# Home_Automation.net
KiCad netlist of a schematic drawn in Altium Designer
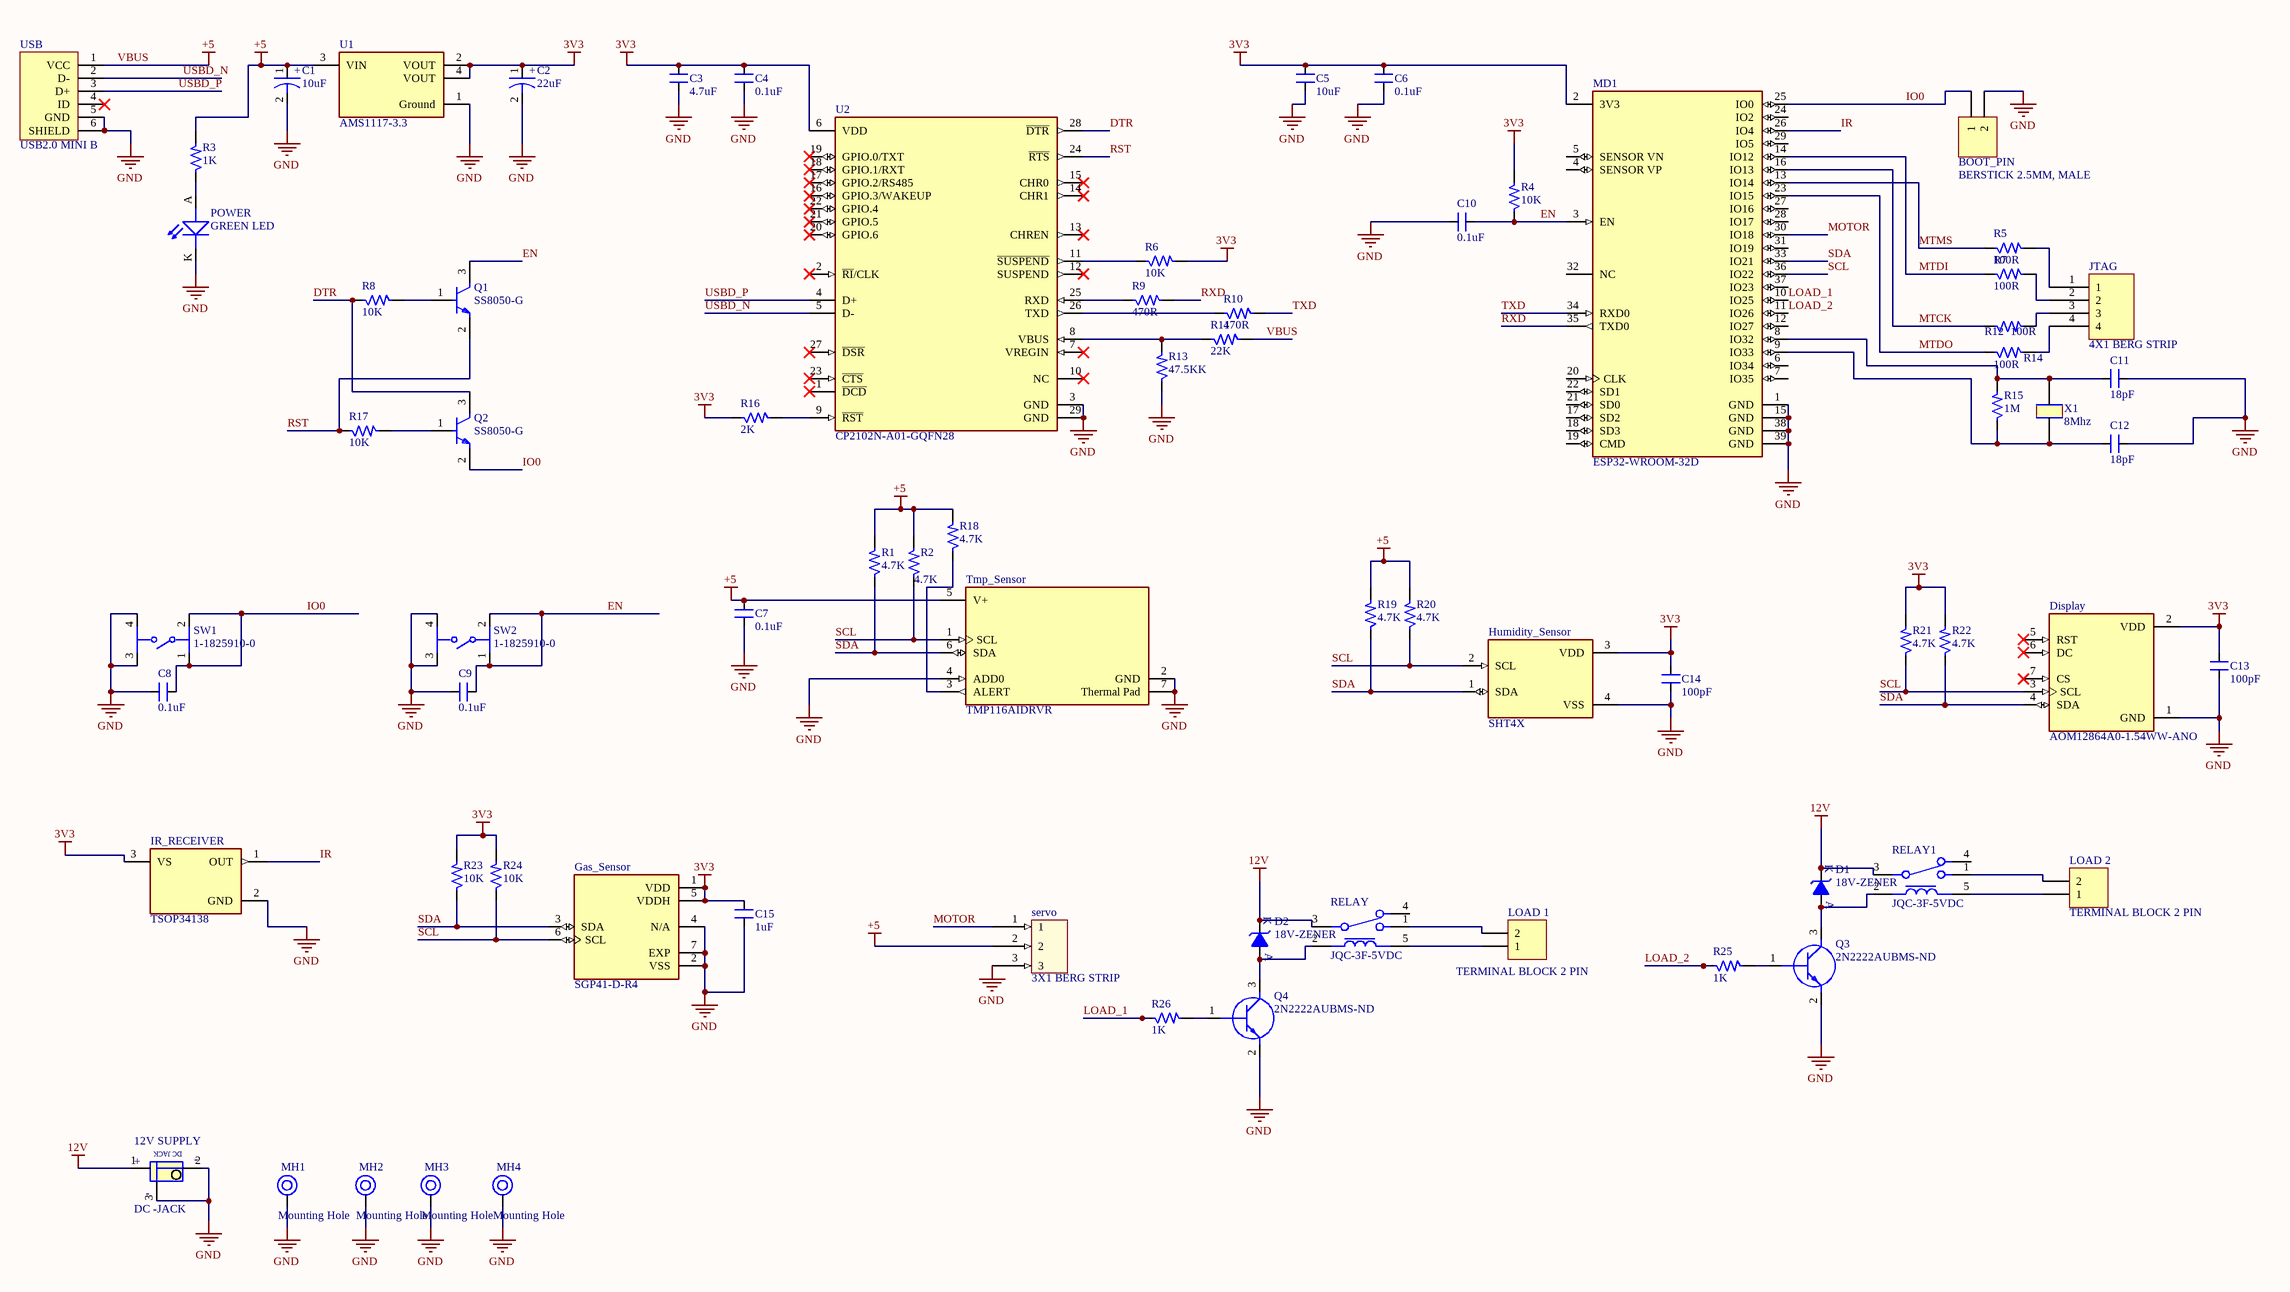
[diagram p0: Home_Automation.SchDoc]

(export (version "E")
  (design (tool "Eeschema 10.0.6"))
  (components
    (comp (ref "12V SUPPLY")
      (value "DC -JACK")
      (footprint "CON3_129_PJ-002A_TH_RA")
      (description "3 Pins, 1 Row 228mil Pitch, right angle Connector, male")
      (fields (field (name "MANUFACTURER") "JST") (field (name "MANUFACTURER PART NUMBER") "PJ-002A"))
      (libsource (lib "ESTEEMPCBLIB") (part "CON-PLG_3X1-228-DC_JACK"))
    )
    (comp (ref "BOOT_PIN")
      (value "BERSTICK 2.5MM, MALE")
      (footprint "CON2_100_43D62_TH_ST")
      (description "2 Pins, 1 Row 2.54mm Pitch, Straight bergstrip, Male")
      (fields (field (name "MANUFACTURER PART NUMBER") "NA") (field (name "MANUFACTURER") "Samtec"))
      (libsource (lib "ESTEEMPCBLIB") (part "CON-BS-PLG_2X1-100-ST-TH"))
    )
    (comp (ref "C1")
      (value "10uF")
      (footprint "ACAP_P339_D393_H531_RAD")
      (description "10µF 400V Aluminum Electrolytic Capacitors Radial, Can - SMD 10000 Hrs @ 105°C")
      (fields
        (field (name "MANUFACTURER") "Nichicon")
        (field (name "MANUFACTURER PART NUMBER") "ULV2G100MNL1GS")
      )
      (libsource (lib "ESTEEMPCBLIB") (part "CAP-P_10uF-400V-20%-RAD"))
    )
    (comp (ref "C2")
      (value "22uF")
      (footprint "ACAP_P339_D393_H531_RAD")
      (description "22µF 400V Aluminum Electrolytic Capacitors Radial, Can - SMD 5000 Hrs @ 105°C")
      (fields
        (field (name "MANUFACTURER") "Panasonic Electronic Components")
        (field (name "MANUFACTURER PART NUMBER") "EEV-EB2G220M")
      )
      (libsource (lib "ESTEEMPCBLIB") (part "CAP-P_22uF-400V-20%-RAD"))
    )
    (comp (ref "C3")
      (value "4.7uF")
      (footprint "CAP_0805")
      (description "4.7µF ±10% 50V Ceramic Capacitor X5R 0805 (2012 Metric)")
      (fields
        (field (name "MANUFACTURER") "Yageo")
        (field (name "MANUFACTURER PART NUMBER") "GRM21BR61H475KE51L")
      )
      (libsource (lib "ESTEEMPCBLIB") (part "CAP_4.7uF-50V-10%-0805"))
    )
    (comp (ref "C4")
      (value "0.1uF")
      (footprint "CAP_0805")
      (description "0.1µF ±10% 50V Ceramic Capacitor X7R 0805 (2012 Metric)")
      (fields
        (field (name "MANUFACTURER") "Samsung")
        (field (name "MANUFACTURER PART NUMBER") "CL21B104KBCNNNC")
      )
      (libsource (lib "ESTEEMPCBLIB") (part "CAP_0.1uF-50V-10%-0805"))
    )
    (comp (ref "C5")
      (value "10uF")
      (footprint "CAP_0805")
      (description "100pF ±5% 100V Ceramic Capacitor C0G, NP0 0805 (2012 Metric)")
      (fields
        (field (name "MANUFACTURER") "Murata")
        (field (name "MANUFACTURER PART NUMBER") "CL21C101JC61PNC")
      )
      (libsource (lib "ESTEEMPCBLIB") (part "CAP_100pF-100V-5%-0805"))
    )
    (comp (ref "C6")
      (value "0.1uF")
      (footprint "CAP_0805")
      (description "0.1µF ±5% 50V Ceramic Capacitor X7R 0805 (2012 Metric)")
      (fields
        (field (name "MANUFACTURER") "AVX Corporation")
        (field (name "MANUFACTURER PART NUMBER") "08055C104JAT4A")
      )
      (libsource (lib "ESTEEMPCBLIB") (part "CAP_0.1uF-50V-5%-0805"))
    )
    (comp (ref "C7")
      (value "0.1uF")
      (footprint "CAP_0805")
      (description "0.1µF ±5% 50V Ceramic Capacitor X7R 0805 (2012 Metric)")
      (fields
        (field (name "MANUFACTURER") "AVX Corporation")
        (field (name "MANUFACTURER PART NUMBER") "08055C104JAT4A")
      )
      (libsource (lib "ESTEEMPCBLIB") (part "CAP_0.1uF-50V-5%-0805"))
    )
    (comp (ref "C8")
      (value "0.1uF")
      (footprint "CAP_0805")
      (description "0.1µF ±5% 50V Ceramic Capacitor X7R 0805 (2012 Metric)")
      (fields
        (field (name "MANUFACTURER") "AVX Corporation")
        (field (name "MANUFACTURER PART NUMBER") "08055C104JAT4A")
      )
      (libsource (lib "ESTEEMPCBLIB") (part "CAP_0.1uF-50V-5%-0805"))
    )
    (comp (ref "C9")
      (value "0.1uF")
      (footprint "CAP_0805")
      (description "0.1µF ±5% 50V Ceramic Capacitor X7R 0805 (2012 Metric)")
      (fields
        (field (name "MANUFACTURER") "AVX Corporation")
        (field (name "MANUFACTURER PART NUMBER") "08055C104JAT4A")
      )
      (libsource (lib "ESTEEMPCBLIB") (part "CAP_0.1uF-50V-5%-0805"))
    )
    (comp (ref "C10")
      (value "0.1uF")
      (footprint "CAP_0805")
      (description "0.1µF ±5% 50V Ceramic Capacitor X7R 0805 (2012 Metric)")
      (fields
        (field (name "MANUFACTURER") "AVX Corporation")
        (field (name "MANUFACTURER PART NUMBER") "08055C104JAT4A")
      )
      (libsource (lib "ESTEEMPCBLIB") (part "CAP_0.1uF-50V-5%-0805"))
    )
    (comp (ref "C11")
      (value "18pF")
      (footprint "CAP_0805")
      (description "18pF ±5% 50V Ceramic Capacitor C0G, NP0 0805 (2012 Metric)")
      (fields
        (field (name "MANUFACTURER") "Yageo")
        (field (name "MANUFACTURER PART NUMBER") "CL21C180JBANNNC")
      )
      (libsource (lib "ESTEEMPCBLIB") (part "CAP_18pF-50V-5%-0805"))
    )
    (comp (ref "C12")
      (value "18pF")
      (footprint "CAP_0805")
      (description "18pF ±5% 50V Ceramic Capacitor C0G, NP0 0805 (2012 Metric)")
      (fields
        (field (name "MANUFACTURER") "Yageo")
        (field (name "MANUFACTURER PART NUMBER") "CL21C180JBANNNC")
      )
      (libsource (lib "ESTEEMPCBLIB") (part "CAP_18pF-50V-5%-0805"))
    )
    (comp (ref "C13")
      (value "100pF")
      (footprint "CAP_0805")
      (description "100pF ±5% 100V Ceramic Capacitor C0G, NP0 0805 (2012 Metric)")
      (fields
        (field (name "MANUFACTURER") "Murata")
        (field (name "MANUFACTURER PART NUMBER") "CL21C101JC61PNC")
      )
      (libsource (lib "ESTEEMPCBLIB") (part "CAP_100pF-100V-5%-0805"))
    )
    (comp (ref "C14")
      (value "100pF")
      (footprint "CAP_0805")
      (description "100pF ±5% 100V Ceramic Capacitor C0G, NP0 0805 (2012 Metric)")
      (fields
        (field (name "MANUFACTURER") "Murata")
        (field (name "MANUFACTURER PART NUMBER") "CL21C101JC61PNC")
      )
      (libsource (lib "ESTEEMPCBLIB") (part "CAP_100pF-100V-5%-0805"))
    )
    (comp (ref "C15")
      (value "1uF")
      (footprint "CAP_0805")
      (description "1µF ±5% 50V Ceramic Capacitor X7R 0805 (2012 Metric)")
      (fields
        (field (name "MANUFACTURER") "Samsung")
        (field (name "MANUFACTURER PART NUMBER") "CC0805JKX7R9BB105")
      )
      (libsource (lib "ESTEEMPCBLIB") (part "CAP_1uF-50V-5%-0805"))
    )
    (comp (ref "D1")
      (value "18V-ZENER")
      (footprint "DIO_SOD80C")
      (description "Zener Diode 18V 500mW ±5% Surface Mount SOD-80 QuadroMELF")
      (fields
        (field (name "MANUFACTURER") "Vishay Semiconductors")
        (field (name "MANUFACTURER PART NUMBER") "BZT55C18-GS08")
      )
      (libsource (lib "ESTEEMPCBLIB") (part "DIO-Z_18V-500mW-SOD80"))
    )
    (comp (ref "D2")
      (value "18V-ZENER")
      (footprint "DIO_SOD80C")
      (description "Zener Diode 18V 500mW ±5% Surface Mount SOD-80 QuadroMELF")
      (fields
        (field (name "MANUFACTURER") "Vishay Semiconductors")
        (field (name "MANUFACTURER PART NUMBER") "BZT55C18-GS08")
      )
      (libsource (lib "ESTEEMPCBLIB") (part "DIO-Z_18V-500mW-SOD80"))
    )
    (comp (ref "Display")
      (value "AOM12864A0-1.54WW-ANO")
      (footprint "LCD_AOM12864A0-1.54WW-ANO")
      (description "Non-Touch Graphic LCD Display Module - White OLED SPI 1.54 (39.12mm) 128 x 64")
      (fields (field (name "MF") "Orient Display"))
      (libsource (lib "AOM12864A0-1.54WW-ANO") (part "AOM12864A0-1.54WW-ANO"))
    )
    (comp (ref "Gas_Sensor")
      (value "SGP41-D-R4")
      (footprint "XDCR_SGP41-D-R4")
      (description "Air Quality Sensor VOC and NOx Gas Sensor 3.3V 6-Pin DFN EP")
      (fields (field (name "MF") "Sensirion"))
      (libsource (lib "SGP41-D-R4") (part "SGP41-D-R4"))
    )
    (comp (ref "Humidity_Sensor")
      (value "SHT4X")
      (footprint "SHT4X")
      (description "Digital Relative Humidity Temperature Sensor, Â±1.0 %RH, Â±0.1 Â°C, Ultra-Low-Power")
      (fields (field (name "MF") "Sensirion") (field (name "MP") "SHT45-AD1B-R2"))
      (libsource (lib "SHT4X") (part "SHT4X"))
    )
    (comp (ref "IR_RECEIVER")
      (value "TSOP34138")
      (footprint "FP-6_550-5169_01-4-MFG")
      (description "SENSOR REMOTE REC 38.0KHZ 45M")
      (fields
        (field (name "MANUFACTURER") "Vishay")
        (field (name "OCTOPART") "https://octopart.com/tsop34138-vishay-55433998")
      )
      (libsource (lib "Altium Content Vault") (part "67e88e076711625980e7b323ec594be"))
    )
    (comp (ref "JTAG")
      (value "4X1 BERG STRIP")
      (footprint "CON4_100_40D72_TH_ST_MALE")
      (description "4 Pins, 1 Row 2.54mm Pitch, Straight bergstrip, Male")
      (fields (field (name "MANUFACTURER") "NA"))
      (libsource (lib "ESTEEMPCBLIB") (part "CON-BS-PLG_4X1-100-ST-TH"))
    )
    (comp (ref "LOAD 1")
      (value "TERMINAL BLOCK 2 PIN")
      (footprint "CON2_P196_1729128_TH_ST")
      (description "2 Pins, 1 Row 5mm Pitch, straight Connector, male")
      (fields
        (field (name "MANUFACTURER") "Phoenix Contact")
        (field (name "MANUFACTURER PART NUMBER") "MKDSN1,5/2")
      )
      (libsource (lib "ESTEEMPCBLIB") (part "CON-TB_2X1-196-ST-TH"))
    )
    (comp (ref "LOAD 2")
      (value "TERMINAL BLOCK 2 PIN")
      (footprint "CON2_P196_1729128_TH_ST")
      (description "2 Pins, 1 Row 5mm Pitch, straight Connector, male")
      (fields
        (field (name "MANUFACTURER") "Phoenix Contact")
        (field (name "MANUFACTURER PART NUMBER") "MKDSN1,5/2")
      )
      (libsource (lib "ESTEEMPCBLIB") (part "CON-TB_2X1-196-ST-TH"))
    )
    (comp (ref "MD1")
      (value "ESP32-WROOM-32D")
      (footprint "FP-ESP32-WROOM-32D-MFG")
      (description "WIFI MODULE 32MBITS SPI FLASH")
      (fields
        (field (name "OCTOPART") "https://octopart.com/esp32-wroom-32d-espressif+systems-91040050")
        (field (name "MANUFACTURER") "Espressif Systems")
      )
      (libsource (lib "Altium Content Vault") (part "a031a76f8c27026a7a7f4657ff233a3"))
    )
    (comp (ref "MH1")
      (value "Mounting Hole")
      (footprint "MOUNTING")
      (fields (field (name "MANUFACTURER PART NUMBER") "NA"))
      (libsource (lib "ESTEEMPCBLIB") (part "MH_3.5H_6D"))
    )
    (comp (ref "MH2")
      (value "Mounting Hole")
      (footprint "MOUNTING")
      (fields (field (name "MANUFACTURER PART NUMBER") "NA"))
      (libsource (lib "ESTEEMPCBLIB") (part "MH_3.5H_6D"))
    )
    (comp (ref "MH3")
      (value "Mounting Hole")
      (footprint "MOUNTING")
      (fields (field (name "MANUFACTURER PART NUMBER") "NA"))
      (libsource (lib "ESTEEMPCBLIB") (part "MH_3.5H_6D"))
    )
    (comp (ref "MH4")
      (value "Mounting Hole")
      (footprint "MOUNTING")
      (fields (field (name "MANUFACTURER PART NUMBER") "NA"))
      (libsource (lib "ESTEEMPCBLIB") (part "MH_3.5H_6D"))
    )
    (comp (ref "POWER")
      (value "GREEN LED")
      (footprint "LED_0805")
      (description "Green 569nm LED Indication - Discrete 2.1V 0805 (2012 Metric)")
      (fields
        (field (name "MANUFACTURER") "Vishay Lite-On")
        (field (name "MANUFACTURER PART NUMBER") "LTST-C171GKT")
      )
      (libsource (lib "ESTEEMPCBLIB") (part "LED_GREEN-2.2-20mA-0805"))
    )
    (comp (ref "Q1")
      (value "SS8050-G")
      (footprint "FP-SS8050-G-MFG")
      (description "NPN TRANSISTOR 1.5A 40V SOT-23 R")
      (libsource (lib "Altium Content Vault") (part "2a1388f82443b098dcd57d24ac7632d"))
    )
    (comp (ref "Q2")
      (value "SS8050-G")
      (footprint "FP-SS8050-G-MFG")
      (description "NPN TRANSISTOR 1.5A 40V SOT-23 R")
      (libsource (lib "Altium Content Vault") (part "2a1388f82443b098dcd57d24ac7632d"))
    )
    (comp (ref "Q3")
      (value "2N2222AUBMS-ND")
      (footprint "SOT 23-3")
      (description "Bipolar (BJT) Transistor NPN 50V 800mA 500mW Surface Mount 3-SMD")
      (fields (field (name "MANUFACTURER") "Microsemi") (field (name "MANUFACTURER PART NUMBER") "2N2222AUB"))
      (libsource (lib "ESTEEMPCBLIB") (part "TRNS-NPN_50V-0.8A-3SMD"))
    )
    (comp (ref "Q4")
      (value "2N2222AUBMS-ND")
      (footprint "SOT 23-3")
      (description "Bipolar (BJT) Transistor NPN 50V 800mA 500mW Surface Mount 3-SMD")
      (fields (field (name "MANUFACTURER") "Microsemi") (field (name "MANUFACTURER PART NUMBER") "2N2222AUB"))
      (libsource (lib "ESTEEMPCBLIB") (part "TRNS-NPN_50V-0.8A-3SMD"))
    )
    (comp (ref "R1")
      (value "4.7K")
      (footprint "RES_0805")
      (description "4.7 kOhms ±1% 0.125W, 1/8W Chip Resistor 0805 (2012 Metric) Moisture Resistant Thick Film")
      (fields
        (field (name "MANUFACTURER") "TE Connectivity")
        (field (name "MANUFACTURER PART NUMBER") "RC0805FR-074K7L")
      )
      (libsource (lib "ESTEEMPCBLIB") (part "RES_4.7K-0.125W-1%-0805"))
    )
    (comp (ref "R2")
      (value "4.7K")
      (footprint "RES_0805")
      (description "4.7 kOhms ±1% 0.125W, 1/8W Chip Resistor 0805 (2012 Metric) Moisture Resistant Thick Film")
      (fields
        (field (name "MANUFACTURER") "TE Connectivity")
        (field (name "MANUFACTURER PART NUMBER") "RC0805FR-074K7L")
      )
      (libsource (lib "ESTEEMPCBLIB") (part "RES_4.7K-0.125W-1%-0805"))
    )
    (comp (ref "R3")
      (value "1K")
      (footprint "RES_0805")
      (description "1 kOhms ±1% 0.125W, 1/8W Chip Resistor 0805 (2012 Metric) Moisture Resistant Thick Film")
      (fields (field (name "MANUFACTURER") "Walsin") (field (name "MANUFACTURER PART NUMBER") "WR08X1001FTL"))
      (libsource (lib "ESTEEMPCBLIB") (part "RES_1K-0.125W-1%-0805"))
    )
    (comp (ref "R4")
      (value "10K")
      (footprint "RES_0805")
      (description "10 kOhms ±1% 0.125W, 1/8W Chip Resistor 0805 (2012 Metric) Automotive AEC-Q200 Thick Film")
      (fields (field (name "MANUFACTURER") "CTS") (field (name "MANUFACTURER PART NUMBER") "WR08X1002FTL"))
      (libsource (lib "ESTEEMPCBLIB") (part "RES_10K-0.125W-1%-0805"))
    )
    (comp (ref "R5")
      (value "100R")
      (footprint "RES_0805")
      (fields (field (name "MANUFACTURER") "Walsin") (field (name "MANUFACTURER PART NUMBER") "WR08X1000FTL"))
      (libsource (lib "ESTEEMPCBLIB") (part "RES_100R-0.125W-1%-0805"))
    )
    (comp (ref "R6")
      (value "10K")
      (footprint "RES_0805")
      (description "10 kOhms ±1% 0.125W, 1/8W Chip Resistor 0805 (2012 Metric) Automotive AEC-Q200 Thick Film")
      (fields (field (name "MANUFACTURER") "CTS") (field (name "MANUFACTURER PART NUMBER") "WR08X1002FTL"))
      (libsource (lib "ESTEEMPCBLIB") (part "RES_10K-0.125W-1%-0805"))
    )
    (comp (ref "R7")
      (value "100R")
      (footprint "RES_0805")
      (fields (field (name "MANUFACTURER") "Walsin") (field (name "MANUFACTURER PART NUMBER") "WR08X1000FTL"))
      (libsource (lib "ESTEEMPCBLIB") (part "RES_100R-0.125W-1%-0805"))
    )
    (comp (ref "R8")
      (value "10K")
      (footprint "RES_0805")
      (description "10 kOhms ±1% 0.125W, 1/8W Chip Resistor 0805 (2012 Metric) Automotive AEC-Q200 Thick Film")
      (fields (field (name "MANUFACTURER") "CTS") (field (name "MANUFACTURER PART NUMBER") "WR08X1002FTL"))
      (libsource (lib "ESTEEMPCBLIB") (part "RES_10K-0.125W-1%-0805"))
    )
    (comp (ref "R9")
      (value "470R")
      (footprint "RES_0805")
      (description "470 Ohms ±1% 0.125W, 1/8W Chip Resistor 0805 (2012 Metric) Automotive AEC-Q200 Thick Film")
      (fields (field (name "MANUFACTURER") "Walsin") (field (name "MANUFACTURER PART NUMBER") "WR08X4700FTL"))
      (libsource (lib "ESTEEMPCBLIB") (part "RES_470R-0.125W-1%-0805"))
    )
    (comp (ref "R10")
      (value "470R")
      (footprint "RES_0805")
      (description "470 Ohms ±1% 0.125W, 1/8W Chip Resistor 0805 (2012 Metric) Automotive AEC-Q200 Thick Film")
      (fields (field (name "MANUFACTURER") "Walsin") (field (name "MANUFACTURER PART NUMBER") "WR08X4700FTL"))
      (libsource (lib "ESTEEMPCBLIB") (part "RES_470R-0.125W-1%-0805"))
    )
    (comp (ref "R11")
      (value "22K")
      (footprint "RES_0805")
      (description "22 kOhms ±1% 0.125W, 1/8W Chip Resistor 0805 (2012 Metric) Automotive AEC-Q200 Thick Film")
      (fields (field (name "MANUFACTURER") "Walsin") (field (name "MANUFACTURER PART NUMBER") "WR08X2202FTL"))
      (libsource (lib "ESTEEMPCBLIB") (part "RES_22K-0.125W-1%-0805"))
    )
    (comp (ref "R12")
      (value "100R")
      (footprint "RES_0805")
      (fields (field (name "MANUFACTURER") "Walsin") (field (name "MANUFACTURER PART NUMBER") "WR08X1000FTL"))
      (libsource (lib "ESTEEMPCBLIB") (part "RES_100R-0.125W-1%-0805"))
    )
    (comp (ref "R13")
      (value "47.5KK")
      (footprint "RES_0805")
      (description "22 kOhms ±1% 0.125W, 1/8W Chip Resistor 0805 (2012 Metric) Automotive AEC-Q200 Thick Film")
      (fields (field (name "MANUFACTURER") "Walsin") (field (name "MANUFACTURER PART NUMBER") "WR08X2202FTL"))
      (libsource (lib "ESTEEMPCBLIB") (part "RES_22K-0.125W-1%-0805"))
    )
    (comp (ref "R14")
      (value "100R")
      (footprint "RES_0805")
      (fields (field (name "MANUFACTURER") "Walsin") (field (name "MANUFACTURER PART NUMBER") "WR08X1000FTL"))
      (libsource (lib "ESTEEMPCBLIB") (part "RES_100R-0.125W-1%-0805"))
    )
    (comp (ref "R15")
      (value "1M")
      (footprint "RES_0805")
      (description "1 MOhms ±1% 0.125W, 1/8W Chip Resistor 0805 (2012 Metric) Automotive AEC-Q200 Thick Film")
      (fields (field (name "MANUFACTURER") "Walsin") (field (name "MANUFACTURER PART NUMBER") "WR08X1004FTL"))
      (libsource (lib "ESTEEMPCBLIB") (part "RES_1M-0.125W-1%-0805"))
    )
    (comp (ref "R16")
      (value "2K")
      (footprint "RES_0805")
      (description "2 kOhms ±1% 0.125W, 1/8W Chip Resistor 0805 (2012 Metric) Moisture Resistant Thick Film")
      (fields
        (field (name "MANUFACTURER") "TE Connectivity")
        (field (name "MANUFACTURER PART NUMBER") "RC0805FR-072KL")
      )
      (libsource (lib "ESTEEMPCBLIB") (part "RES_2K-0.125W-1%-0805"))
    )
    (comp (ref "R17")
      (value "10K")
      (footprint "RES_0805")
      (description "10 kOhms ±1% 0.125W, 1/8W Chip Resistor 0805 (2012 Metric) Automotive AEC-Q200 Thick Film")
      (fields (field (name "MANUFACTURER") "CTS") (field (name "MANUFACTURER PART NUMBER") "WR08X1002FTL"))
      (libsource (lib "ESTEEMPCBLIB") (part "RES_10K-0.125W-1%-0805"))
    )
    (comp (ref "R18")
      (value "4.7K")
      (footprint "RES_0805")
      (description "4.7 kOhms ±1% 0.125W, 1/8W Chip Resistor 0805 (2012 Metric) Moisture Resistant Thick Film")
      (fields
        (field (name "MANUFACTURER") "TE Connectivity")
        (field (name "MANUFACTURER PART NUMBER") "RC0805FR-074K7L")
      )
      (libsource (lib "ESTEEMPCBLIB") (part "RES_4.7K-0.125W-1%-0805"))
    )
    (comp (ref "R19")
      (value "4.7K")
      (footprint "RES_0805")
      (description "4.7 kOhms ±1% 0.125W, 1/8W Chip Resistor 0805 (2012 Metric) Moisture Resistant Thick Film")
      (fields
        (field (name "MANUFACTURER") "TE Connectivity")
        (field (name "MANUFACTURER PART NUMBER") "RC0805FR-074K7L")
      )
      (libsource (lib "ESTEEMPCBLIB") (part "RES_4.7K-0.125W-1%-0805"))
    )
    (comp (ref "R20")
      (value "4.7K")
      (footprint "RES_0805")
      (description "4.7 kOhms ±1% 0.125W, 1/8W Chip Resistor 0805 (2012 Metric) Moisture Resistant Thick Film")
      (fields
        (field (name "MANUFACTURER") "TE Connectivity")
        (field (name "MANUFACTURER PART NUMBER") "RC0805FR-074K7L")
      )
      (libsource (lib "ESTEEMPCBLIB") (part "RES_4.7K-0.125W-1%-0805"))
    )
    (comp (ref "R21")
      (value "4.7K")
      (footprint "RES_0805")
      (description "4.7 kOhms ±1% 0.125W, 1/8W Chip Resistor 0805 (2012 Metric) Moisture Resistant Thick Film")
      (fields
        (field (name "MANUFACTURER") "TE Connectivity")
        (field (name "MANUFACTURER PART NUMBER") "RC0805FR-074K7L")
      )
      (libsource (lib "ESTEEMPCBLIB") (part "RES_4.7K-0.125W-1%-0805"))
    )
    (comp (ref "R22")
      (value "4.7K")
      (footprint "RES_0805")
      (description "4.7 kOhms ±1% 0.125W, 1/8W Chip Resistor 0805 (2012 Metric) Moisture Resistant Thick Film")
      (fields
        (field (name "MANUFACTURER") "TE Connectivity")
        (field (name "MANUFACTURER PART NUMBER") "RC0805FR-074K7L")
      )
      (libsource (lib "ESTEEMPCBLIB") (part "RES_4.7K-0.125W-1%-0805"))
    )
    (comp (ref "R23")
      (value "10K")
      (footprint "RES_0805")
      (description "10 kOhms ±1% 0.125W, 1/8W Chip Resistor 0805 (2012 Metric) Automotive AEC-Q200 Thick Film")
      (fields (field (name "MANUFACTURER") "CTS") (field (name "MANUFACTURER PART NUMBER") "WR08X1002FTL"))
      (libsource (lib "ESTEEMPCBLIB") (part "RES_10K-0.125W-1%-0805"))
    )
    (comp (ref "R24")
      (value "10K")
      (footprint "RES_0805")
      (description "10 kOhms ±1% 0.125W, 1/8W Chip Resistor 0805 (2012 Metric) Automotive AEC-Q200 Thick Film")
      (fields (field (name "MANUFACTURER") "CTS") (field (name "MANUFACTURER PART NUMBER") "WR08X1002FTL"))
      (libsource (lib "ESTEEMPCBLIB") (part "RES_10K-0.125W-1%-0805"))
    )
    (comp (ref "R25")
      (value "1K")
      (footprint "RES_0805")
      (description "1 kOhms ±1% 0.125W, 1/8W Chip Resistor 0805 (2012 Metric) Moisture Resistant Thick Film")
      (fields (field (name "MANUFACTURER") "Walsin") (field (name "MANUFACTURER PART NUMBER") "WR08X1001FTL"))
      (libsource (lib "ESTEEMPCBLIB") (part "RES_1K-0.125W-1%-0805"))
    )
    (comp (ref "R26")
      (value "1K")
      (footprint "RES_0805")
      (description "1 kOhms ±1% 0.125W, 1/8W Chip Resistor 0805 (2012 Metric) Moisture Resistant Thick Film")
      (fields (field (name "MANUFACTURER") "Walsin") (field (name "MANUFACTURER PART NUMBER") "WR08X1001FTL"))
      (libsource (lib "ESTEEMPCBLIB") (part "RES_1K-0.125W-1%-0805"))
    )
    (comp (ref "RELAY")
      (value "JQC-3F-5VDC")
      (footprint "RLY_JQC_3F_5VDC")
      (description "5V DC RELAY 2 CHANNEL")
      (fields (field (name "MANUFACTURER") "YUEQING HENGWEI ELECTRONICS"))
      (libsource (lib "ESTEEMPCBLIB") (part "RLY2_5V-7.5A"))
    )
    (comp (ref "RELAY1")
      (value "JQC-3F-5VDC")
      (footprint "RLY_JQC_3F_5VDC")
      (description "5V DC RELAY 2 CHANNEL")
      (fields (field (name "MANUFACTURER") "YUEQING HENGWEI ELECTRONICS"))
      (libsource (lib "ESTEEMPCBLIB") (part "RLY2_5V-7.5A"))
    )
    (comp (ref "servo")
      (value "3X1 BERG STRIP")
      (footprint "CON3_100_40D72_TH_ST-MALE")
      (description "3 Pins, 1 Row 2.54mm Pitch, Straight bergstrip, Male")
      (fields (field (name "MANUFACTURER PART NUMBER") "RKI-1140") (field (name "MANUFACTURER") "NA"))
      (libsource (lib "ESTEEMPCBLIB") (part "CON-BS-PLG_3X1-100-ST-TH"))
    )
    (comp (ref "SW1")
      (value "1-1825910-0")
      (footprint "FP-1-1825910-0-MFG")
      (description "SWITCH TACTILE SPST-NO 0.05A 24V")
      (libsource (lib "Altium Content Vault") (part "b8895f3f4cefb76e1819d2863dba89b"))
    )
    (comp (ref "SW2")
      (value "1-1825910-0")
      (footprint "FP-1-1825910-0-MFG")
      (description "SWITCH TACTILE SPST-NO 0.05A 24V")
      (libsource (lib "Altium Content Vault") (part "b8895f3f4cefb76e1819d2863dba89b"))
    )
    (comp (ref "Tmp_Sensor")
      (value "TMP116AIDRVR")
      (footprint "FP-DRV0006A-IPC_C")
      (description "SENSOR DIGITAL -55C-125C 6WSON")
      (libsource (lib "Altium Content Vault") (part "a617691ba8d4fd78c31dab07a1f4092"))
    )
    (comp (ref "U1")
      (value "AMS1117-3.3")
      (footprint "FP-AMS1117-IPC_C")
      (description "LDO Voltage Regulators 1A, 3.3V")
      (fields
        (field (name "OCTOPART") "https://octopart.com/ams1117-3.3-advanced+monolithic+systems-25899300")
        (field (name "MANUFACTURER") "Advanced Monolithic Systems")
      )
      (libsource (lib "Altium Content Vault") (part "8bdbb5f8e77002000e30dd2845d0354"))
    )
    (comp (ref "U2")
      (value "CP2102N-A01-GQFN28")
      (footprint "FP-CP2102N-A01-GQFN28-MFG")
      (description "IC BRIDGE USB TO UART 28QFN")
      (fields
        (field (name "MANUFACTURER") "Silicon Labs")
        (field (name "OCTOPART") "https://octopart.com/cp2102n-a01-gqfn28-silicon+labs-74636024")
      )
      (libsource (lib "Altium Content Vault") (part "9ca185fe47a6ee51fa7191d999467af"))
    )
    (comp (ref "USB")
      (value "USB2.0 MINI B")
      (footprint "CON_690-005-299-043")
      (description "USB - mini B USB 2.0 Receptacle Connector 5 Position Surface Mount, Right Angle")
      (fields
        (field (name "MANUFACTURER") "EDAC")
        (field (name "MANUFACTURER PART NUMBER") "690-005-299-043")
      )
      (libsource (lib "ESTEEMPCBLIB") (part "CON_USB2.0-MINIB-SMD"))
    )
    (comp (ref "X1")
      (value "8Mhz")
      (footprint "XTAL_314_240X47_SMD")
      (description "8MHz ±30ppm Crystal 32pF 60 Ohms HC-49/US")
      (fields
        (field (name "MANUFACTURER") "Fox Electronics")
        (field (name "MANUFACTURER PART NUMBER") "ECS-80-32-5PX-TR")
      )
      (libsource (lib "ESTEEMPCBLIB") (part "XTAL_8MHZ-ECS-80-32-5PX-SMD"))
    )
  )
  (nets
    (net (code "1") (name "+5") (class "Default")
      (node (ref "C1") (pin "1") (pinfunction "1_1") (pintype "passive"))
      (node (ref "C7") (pin "2") (pinfunction "2_2") (pintype "passive"))
      (node (ref "R1") (pin "2") (pinfunction "2_2") (pintype "passive"))
      (node (ref "R11") (pin "2") (pinfunction "2_2") (pintype "passive"))
      (node (ref "R18") (pin "2") (pinfunction "2_2") (pintype "passive"))
      (node (ref "R19") (pin "2") (pinfunction "2_2") (pintype "passive"))
      (node (ref "R2") (pin "2") (pinfunction "2_2") (pintype "passive"))
      (node (ref "R20") (pin "2") (pinfunction "2_2") (pintype "passive"))
      (node (ref "R3") (pin "2") (pinfunction "2_2") (pintype "passive"))
      (node (ref "Tmp_Sensor") (pin "5") (pinfunction "V+_5") (pintype "power_in"))
      (node (ref "U1") (pin "3") (pinfunction "VIN_3") (pintype "power_in"))
      (node (ref "USB") (pin "1") (pinfunction "VCC_1") (pintype "passive"))
      (node (ref "servo") (pin "2") (pinfunction "2_2") (pintype "input"))
    )
    (net (code "2") (name "/DTR") (class "Default")
      (node (ref "Q2") (pin "3") (pinfunction "C_3") (pintype "passive"))
      (node (ref "R8") (pin "1") (pinfunction "1_1") (pintype "passive"))
      (node (ref "U2") (pin "28") (pinfunction "~{DTR}_28") (pintype "output"))
    )
    (net (code "3") (name "/EN") (class "Default")
      (node (ref "C10") (pin "1") (pinfunction "1_1") (pintype "passive"))
      (node (ref "C9") (pin "2") (pinfunction "2_2") (pintype "passive"))
      (node (ref "MD1") (pin "3") (pinfunction "EN_3") (pintype "input"))
      (node (ref "Q1") (pin "3") (pinfunction "C_3") (pintype "passive"))
      (node (ref "R4") (pin "1") (pinfunction "1_1") (pintype "passive"))
      (node (ref "SW2") (pin "1") (pinfunction "1_1") (pintype "passive"))
      (node (ref "SW2") (pin "2") (pinfunction "2_2") (pintype "passive"))
    )
    (net (code "4") (name "/IO0") (class "Default")
      (node (ref "BOOT_PIN") (pin "1") (pinfunction "1_1") (pintype "passive"))
      (node (ref "C8") (pin "2") (pinfunction "2_2") (pintype "passive"))
      (node (ref "MD1") (pin "25") (pinfunction "IO0_25") (pintype "bidirectional"))
      (node (ref "Q2") (pin "2") (pinfunction "E_2") (pintype "passive"))
      (node (ref "SW1") (pin "1") (pinfunction "1_1") (pintype "passive"))
      (node (ref "SW1") (pin "2") (pinfunction "2_2") (pintype "passive"))
    )
    (net (code "5") (name "/IR") (class "Default")
      (node (ref "IR_RECEIVER") (pin "1") (pinfunction "OUT_1") (pintype "output"))
      (node (ref "MD1") (pin "26") (pinfunction "IO4_26") (pintype "bidirectional"))
    )
    (net (code "6") (name "/LOAD_1") (class "Default")
      (node (ref "MD1") (pin "10") (pinfunction "IO25_10") (pintype "bidirectional"))
      (node (ref "R26") (pin "1") (pinfunction "1_1") (pintype "passive"))
    )
    (net (code "7") (name "/LOAD_2") (class "Default")
      (node (ref "MD1") (pin "11") (pinfunction "IO26_11") (pintype "bidirectional"))
      (node (ref "R25") (pin "1") (pinfunction "1_1") (pintype "passive"))
    )
    (net (code "8") (name "/MOTOR") (class "Default")
      (node (ref "MD1") (pin "30") (pinfunction "IO18_30") (pintype "bidirectional"))
      (node (ref "servo") (pin "1") (pinfunction "1_1") (pintype "input"))
    )
    (net (code "9") (name "/MTCK") (class "Default")
      (node (ref "MD1") (pin "16") (pinfunction "IO13_16") (pintype "bidirectional"))
      (node (ref "R12") (pin "1") (pinfunction "1_1") (pintype "passive"))
    )
    (net (code "10") (name "/MTDI") (class "Default")
      (node (ref "MD1") (pin "14") (pinfunction "IO12_14") (pintype "bidirectional"))
      (node (ref "R7") (pin "1") (pinfunction "1_1") (pintype "passive"))
    )
    (net (code "11") (name "/MTDO") (class "Default")
      (node (ref "MD1") (pin "23") (pinfunction "IO15_23") (pintype "bidirectional"))
      (node (ref "R14") (pin "1") (pinfunction "1_1") (pintype "passive"))
    )
    (net (code "12") (name "/MTMS") (class "Default")
      (node (ref "MD1") (pin "13") (pinfunction "IO14_13") (pintype "bidirectional"))
      (node (ref "R5") (pin "1") (pinfunction "1_1") (pintype "passive"))
    )
    (net (code "13") (name "/RST") (class "Default")
      (node (ref "Q1") (pin "2") (pinfunction "E_2") (pintype "passive"))
      (node (ref "R17") (pin "1") (pinfunction "1_1") (pintype "passive"))
      (node (ref "U2") (pin "24") (pinfunction "~{RTS}_24") (pintype "output"))
    )
    (net (code "14") (name "/RXD") (class "Default")
      (node (ref "MD1") (pin "35") (pinfunction "TXD0_35") (pintype "output"))
      (node (ref "R9") (pin "2") (pinfunction "2_2") (pintype "passive"))
    )
    (net (code "15") (name "/SCL") (class "Default")
      (node (ref "Display") (pin "3") (pinfunction "SCL_3") (pintype "input"))
      (node (ref "Gas_Sensor") (pin "6") (pinfunction "SCL_6") (pintype "bidirectional"))
      (node (ref "Humidity_Sensor") (pin "2") (pinfunction "SCL_2") (pintype "input"))
      (node (ref "MD1") (pin "36") (pinfunction "IO22_36") (pintype "bidirectional"))
      (node (ref "R2") (pin "1") (pinfunction "1_1") (pintype "passive"))
      (node (ref "R20") (pin "1") (pinfunction "1_1") (pintype "passive"))
      (node (ref "R21") (pin "1") (pinfunction "1_1") (pintype "passive"))
      (node (ref "R24") (pin "1") (pinfunction "1_1") (pintype "passive"))
      (node (ref "Tmp_Sensor") (pin "1") (pinfunction "SCL_1") (pintype "input"))
    )
    (net (code "16") (name "/SDA") (class "Default")
      (node (ref "Display") (pin "4") (pinfunction "SDA_4") (pintype "bidirectional"))
      (node (ref "Gas_Sensor") (pin "3") (pinfunction "SDA_3") (pintype "bidirectional"))
      (node (ref "Humidity_Sensor") (pin "1") (pinfunction "SDA_1") (pintype "bidirectional"))
      (node (ref "MD1") (pin "33") (pinfunction "IO21_33") (pintype "bidirectional"))
      (node (ref "R1") (pin "1") (pinfunction "1_1") (pintype "passive"))
      (node (ref "R19") (pin "1") (pinfunction "1_1") (pintype "passive"))
      (node (ref "R22") (pin "1") (pinfunction "1_1") (pintype "passive"))
      (node (ref "R23") (pin "1") (pinfunction "1_1") (pintype "passive"))
      (node (ref "Tmp_Sensor") (pin "6") (pinfunction "SDA_6") (pintype "bidirectional"))
    )
    (net (code "17") (name "/TXD") (class "Default")
      (node (ref "MD1") (pin "34") (pinfunction "RXD0_34") (pintype "input"))
      (node (ref "R10") (pin "2") (pinfunction "2_2") (pintype "passive"))
    )
    (net (code "18") (name "/USBD_N") (class "Default")
      (node (ref "U2") (pin "5") (pinfunction "D-_5") (pintype "passive"))
      (node (ref "USB") (pin "2") (pinfunction "D-_2") (pintype "passive"))
    )
    (net (code "19") (name "/USBD_P") (class "Default")
      (node (ref "U2") (pin "4") (pinfunction "D+_4") (pintype "passive"))
      (node (ref "USB") (pin "3") (pinfunction "D+_3") (pintype "passive"))
    )
    (net (code "20") (name "3V3") (class "Default")
      (node (ref "C13") (pin "2") (pinfunction "2_2") (pintype "passive"))
      (node (ref "C14") (pin "2") (pinfunction "2_2") (pintype "passive"))
      (node (ref "C15") (pin "2") (pinfunction "2_2") (pintype "passive"))
      (node (ref "C2") (pin "1") (pinfunction "1_1") (pintype "passive"))
      (node (ref "C3") (pin "2") (pinfunction "2_2") (pintype "passive"))
      (node (ref "C4") (pin "2") (pinfunction "2_2") (pintype "passive"))
      (node (ref "C5") (pin "2") (pinfunction "2_2") (pintype "passive"))
      (node (ref "C6") (pin "2") (pinfunction "2_2") (pintype "passive"))
      (node (ref "Display") (pin "2") (pinfunction "VDD_2") (pintype "power_in"))
      (node (ref "Gas_Sensor") (pin "1") (pinfunction "VDD_1") (pintype "power_in"))
      (node (ref "Gas_Sensor") (pin "5") (pinfunction "VDDH_5") (pintype "power_in"))
      (node (ref "Humidity_Sensor") (pin "3") (pinfunction "VDD_3") (pintype "power_in"))
      (node (ref "IR_RECEIVER") (pin "3") (pinfunction "VS_3") (pintype "power_in"))
      (node (ref "MD1") (pin "2") (pinfunction "3V3_2") (pintype "power_in"))
      (node (ref "R16") (pin "1") (pinfunction "1_1") (pintype "passive"))
      (node (ref "R21") (pin "2") (pinfunction "2_2") (pintype "passive"))
      (node (ref "R22") (pin "2") (pinfunction "2_2") (pintype "passive"))
      (node (ref "R23") (pin "2") (pinfunction "2_2") (pintype "passive"))
      (node (ref "R24") (pin "2") (pinfunction "2_2") (pintype "passive"))
      (node (ref "R4") (pin "2") (pinfunction "2_2") (pintype "passive"))
      (node (ref "R6") (pin "2") (pinfunction "2_2") (pintype "passive"))
      (node (ref "U1") (pin "2") (pinfunction "VOUT_2") (pintype "passive"))
      (node (ref "U1") (pin "4") (pinfunction "VOUT_4") (pintype "passive"))
      (node (ref "U2") (pin "6") (pinfunction "VDD_6") (pintype "power_in"))
    )
    (net (code "21") (name "12V") (class "Default")
      (node (ref "12V SUPPLY") (pin "1") (pinfunction "1_1") (pintype "passive"))
      (node (ref "D1") (pin "K") (pinfunction "K_K") (pintype "passive"))
      (node (ref "D2") (pin "K") (pinfunction "K_K") (pintype "passive"))
      (node (ref "RELAY") (pin "3") (pinfunction "3_3") (pintype "passive"))
      (node (ref "RELAY1") (pin "3") (pinfunction "3_3") (pintype "passive"))
    )
    (net (code "22") (name "GND") (class "Default")
      (node (ref "12V SUPPLY") (pin "2") (pinfunction "2_2") (pintype "passive"))
      (node (ref "12V SUPPLY") (pin "3") (pinfunction "-_3") (pintype "passive"))
      (node (ref "BOOT_PIN") (pin "2") (pinfunction "2_2") (pintype "passive"))
      (node (ref "C1") (pin "2") (pinfunction "2_2") (pintype "passive"))
      (node (ref "C10") (pin "2") (pinfunction "2_2") (pintype "passive"))
      (node (ref "C11") (pin "2") (pinfunction "2_2") (pintype "passive"))
      (node (ref "C12") (pin "2") (pinfunction "2_2") (pintype "passive"))
      (node (ref "C13") (pin "1") (pinfunction "1_1") (pintype "passive"))
      (node (ref "C14") (pin "1") (pinfunction "1_1") (pintype "passive"))
      (node (ref "C15") (pin "1") (pinfunction "1_1") (pintype "passive"))
      (node (ref "C2") (pin "2") (pinfunction "2_2") (pintype "passive"))
      (node (ref "C3") (pin "1") (pinfunction "1_1") (pintype "passive"))
      (node (ref "C4") (pin "1") (pinfunction "1_1") (pintype "passive"))
      (node (ref "C5") (pin "1") (pinfunction "1_1") (pintype "passive"))
      (node (ref "C6") (pin "1") (pinfunction "1_1") (pintype "passive"))
      (node (ref "C7") (pin "1") (pinfunction "1_1") (pintype "passive"))
      (node (ref "C8") (pin "1") (pinfunction "1_1") (pintype "passive"))
      (node (ref "C9") (pin "1") (pinfunction "1_1") (pintype "passive"))
      (node (ref "Display") (pin "1") (pinfunction "GND_1") (pintype "power_in"))
      (node (ref "Gas_Sensor") (pin "2") (pinfunction "VSS_2") (pintype "power_in"))
      (node (ref "Gas_Sensor") (pin "4") (pinfunction "N/A_4") (pintype "passive"))
      (node (ref "Gas_Sensor") (pin "7") (pinfunction "EXP_7") (pintype "power_in"))
      (node (ref "Humidity_Sensor") (pin "4") (pinfunction "VSS_4") (pintype "power_in"))
      (node (ref "IR_RECEIVER") (pin "2") (pinfunction "GND_2") (pintype "power_in"))
      (node (ref "MD1") (pin "1") (pinfunction "GND_1") (pintype "power_in"))
      (node (ref "MD1") (pin "15") (pinfunction "GND_15") (pintype "power_in"))
      (node (ref "MD1") (pin "38") (pinfunction "GND_38") (pintype "power_in"))
      (node (ref "MD1") (pin "39") (pinfunction "GND_39") (pintype "power_in"))
      (node (ref "MH1") (pin "1") (pinfunction "1_1") (pintype "passive"))
      (node (ref "MH2") (pin "1") (pinfunction "1_1") (pintype "passive"))
      (node (ref "MH3") (pin "1") (pinfunction "1_1") (pintype "passive"))
      (node (ref "MH4") (pin "1") (pinfunction "1_1") (pintype "passive"))
      (node (ref "POWER") (pin "K") (pinfunction "CATHODE_K") (pintype "passive"))
      (node (ref "Q3") (pin "2") (pinfunction "E_2") (pintype "passive"))
      (node (ref "Q4") (pin "2") (pinfunction "E_2") (pintype "passive"))
      (node (ref "R13") (pin "1") (pinfunction "1_1") (pintype "passive"))
      (node (ref "SW1") (pin "3") (pinfunction "3_3") (pintype "passive"))
      (node (ref "SW1") (pin "4") (pinfunction "4_4") (pintype "passive"))
      (node (ref "SW2") (pin "3") (pinfunction "3_3") (pintype "passive"))
      (node (ref "SW2") (pin "4") (pinfunction "4_4") (pintype "passive"))
      (node (ref "Tmp_Sensor") (pin "2") (pinfunction "GND_2") (pintype "power_in"))
      (node (ref "Tmp_Sensor") (pin "4") (pinfunction "ADD0_4") (pintype "input"))
      (node (ref "Tmp_Sensor") (pin "7") (pinfunction "Thermal_Pad_7") (pintype "passive"))
      (node (ref "U1") (pin "1") (pinfunction "Ground_1") (pintype "power_in"))
      (node (ref "U2") (pin "29") (pinfunction "GND_29") (pintype "power_in"))
      (node (ref "U2") (pin "3") (pinfunction "GND_3") (pintype "power_in"))
      (node (ref "USB") (pin "5") (pinfunction "GND_5") (pintype "passive"))
      (node (ref "USB") (pin "6") (pinfunction "SHIELD_6") (pintype "passive"))
      (node (ref "servo") (pin "3") (pinfunction "3_3") (pintype "input"))
    )
    (net (code "23") (name "Net-(JTAG-Pad1)") (class "Default")
      (node (ref "JTAG") (pin "1") (pinfunction "1_1") (pintype "passive"))
      (node (ref "R5") (pin "2") (pinfunction "2_2") (pintype "passive"))
    )
    (net (code "24") (name "Net-(JTAG-Pad2)") (class "Default")
      (node (ref "JTAG") (pin "2") (pinfunction "2_2") (pintype "passive"))
      (node (ref "R7") (pin "2") (pinfunction "2_2") (pintype "passive"))
    )
    (net (code "25") (name "Net-(JTAG-Pad3)") (class "Default")
      (node (ref "JTAG") (pin "3") (pinfunction "3_3") (pintype "passive"))
      (node (ref "R12") (pin "2") (pinfunction "2_2") (pintype "passive"))
    )
    (net (code "26") (name "Net-(JTAG-Pad4)") (class "Default")
      (node (ref "JTAG") (pin "4") (pinfunction "4_4") (pintype "passive"))
      (node (ref "R14") (pin "2") (pinfunction "2_2") (pintype "passive"))
    )
    (net (code "27") (name "Net-(LOAD 1-Pad1)") (class "Default")
      (node (ref "LOAD 1") (pin "1") (pinfunction "1_1") (pintype "passive"))
      (node (ref "RELAY") (pin "5") (pinfunction "5_5") (pintype "passive"))
    )
    (net (code "28") (name "Net-(LOAD 1-Pad2)") (class "Default")
      (node (ref "LOAD 1") (pin "2") (pinfunction "2_2") (pintype "passive"))
      (node (ref "RELAY") (pin "1") (pinfunction "1_1") (pintype "passive"))
    )
    (net (code "29") (name "Net-(LOAD 2-Pad1)") (class "Default")
      (node (ref "LOAD 2") (pin "1") (pinfunction "1_1") (pintype "passive"))
      (node (ref "RELAY1") (pin "5") (pinfunction "5_5") (pintype "passive"))
    )
    (net (code "30") (name "Net-(LOAD 2-Pad2)") (class "Default")
      (node (ref "LOAD 2") (pin "2") (pinfunction "2_2") (pintype "passive"))
      (node (ref "RELAY1") (pin "1") (pinfunction "1_1") (pintype "passive"))
    )
    (net (code "31") (name "Net-(MD1-IO32)") (class "Default")
      (node (ref "C11") (pin "1") (pinfunction "1_1") (pintype "passive"))
      (node (ref "MD1") (pin "8") (pinfunction "IO32_8") (pintype "bidirectional"))
      (node (ref "R15") (pin "2") (pinfunction "2_2") (pintype "passive"))
      (node (ref "X1") (pin "2") (pinfunction "2_2") (pintype "passive"))
    )
    (net (code "32") (name "Net-(MD1-IO33)") (class "Default")
      (node (ref "C12") (pin "1") (pinfunction "1_1") (pintype "passive"))
      (node (ref "MD1") (pin "9") (pinfunction "IO33_9") (pintype "bidirectional"))
      (node (ref "R15") (pin "1") (pinfunction "1_1") (pintype "passive"))
      (node (ref "X1") (pin "1") (pinfunction "1_1") (pintype "passive"))
    )
    (net (code "33") (name "Net-(POWER-ANODE)") (class "Default")
      (node (ref "POWER") (pin "A") (pinfunction "ANODE_A") (pintype "passive"))
      (node (ref "R3") (pin "1") (pinfunction "1_1") (pintype "passive"))
    )
    (net (code "34") (name "Net-(Q1-B)") (class "Default")
      (node (ref "Q1") (pin "1") (pinfunction "B_1") (pintype "passive"))
      (node (ref "R8") (pin "2") (pinfunction "2_2") (pintype "passive"))
    )
    (net (code "35") (name "Net-(Q2-B)") (class "Default")
      (node (ref "Q2") (pin "1") (pinfunction "B_1") (pintype "passive"))
      (node (ref "R17") (pin "2") (pinfunction "2_2") (pintype "passive"))
    )
    (net (code "36") (name "Net-(Q3-B)") (class "Default")
      (node (ref "Q3") (pin "1") (pinfunction "B_1") (pintype "passive"))
      (node (ref "R25") (pin "2") (pinfunction "2_2") (pintype "passive"))
    )
    (net (code "37") (name "Net-(Q3-C)") (class "Default")
      (node (ref "D1") (pin "A") (pinfunction "A_A") (pintype "passive"))
      (node (ref "Q3") (pin "3") (pinfunction "C_3") (pintype "passive"))
      (node (ref "RELAY1") (pin "2") (pinfunction "2_2") (pintype "passive"))
    )
    (net (code "38") (name "Net-(Q4-B)") (class "Default")
      (node (ref "Q4") (pin "1") (pinfunction "B_1") (pintype "passive"))
      (node (ref "R26") (pin "2") (pinfunction "2_2") (pintype "passive"))
    )
    (net (code "39") (name "Net-(Q4-C)") (class "Default")
      (node (ref "D2") (pin "A") (pinfunction "A_A") (pintype "passive"))
      (node (ref "Q4") (pin "3") (pinfunction "C_3") (pintype "passive"))
      (node (ref "RELAY") (pin "2") (pinfunction "2_2") (pintype "passive"))
    )
    (net (code "40") (name "Net-(Tmp_Sensor-ALERT)") (class "Default")
      (node (ref "R18") (pin "1") (pinfunction "1_1") (pintype "passive"))
      (node (ref "Tmp_Sensor") (pin "3") (pinfunction "ALERT_3") (pintype "output"))
    )
    (net (code "41") (name "Net-(U2-RXD)") (class "Default")
      (node (ref "R9") (pin "1") (pinfunction "1_1") (pintype "passive"))
      (node (ref "U2") (pin "25") (pinfunction "RXD_25") (pintype "input"))
    )
    (net (code "42") (name "Net-(U2-TXD)") (class "Default")
      (node (ref "R10") (pin "1") (pinfunction "1_1") (pintype "passive"))
      (node (ref "U2") (pin "26") (pinfunction "TXD_26") (pintype "output"))
    )
    (net (code "43") (name "Net-(U2-VBUS)") (class "Default")
      (node (ref "R11") (pin "1") (pinfunction "1_1") (pintype "passive"))
      (node (ref "R13") (pin "2") (pinfunction "2_2") (pintype "passive"))
      (node (ref "U2") (pin "8") (pinfunction "VBUS_8") (pintype "input"))
    )
    (net (code "44") (name "Net-(U2-~{RST})") (class "Default")
      (node (ref "R16") (pin "2") (pinfunction "2_2") (pintype "passive"))
      (node (ref "U2") (pin "9") (pinfunction "~{RST}_9") (pintype "input"))
    )
    (net (code "45") (name "Net-(U2-~{SUSPEND})") (class "Default")
      (node (ref "R6") (pin "1") (pinfunction "1_1") (pintype "passive"))
      (node (ref "U2") (pin "11") (pinfunction "~{SUSPEND}_11") (pintype "output"))
    )
    (net (code "46") (name "unconnected-(Display-CS-Pad7)") (class "Default")
      (node (ref "Display") (pin "7") (pinfunction "CS_7") (pintype "input+no_connect"))
    )
    (net (code "47") (name "unconnected-(Display-DC-Pad6)") (class "Default")
      (node (ref "Display") (pin "6") (pinfunction "DC_6") (pintype "input+no_connect"))
    )
    (net (code "48") (name "unconnected-(Display-RST-Pad5)") (class "Default")
      (node (ref "Display") (pin "5") (pinfunction "RST_5") (pintype "input+no_connect"))
    )
    (net (code "49") (name "unconnected-(MD1-CLK-Pad20)") (class "Default")
      (node (ref "MD1") (pin "20") (pinfunction "CLK_20") (pintype "input"))
    )
    (net (code "50") (name "unconnected-(MD1-CMD-Pad19)") (class "Default")
      (node (ref "MD1") (pin "19") (pinfunction "CMD_19") (pintype "bidirectional"))
    )
    (net (code "51") (name "unconnected-(MD1-IO2-Pad24)") (class "Default")
      (node (ref "MD1") (pin "24") (pinfunction "IO2_24") (pintype "bidirectional"))
    )
    (net (code "52") (name "unconnected-(MD1-IO5-Pad29)") (class "Default")
      (node (ref "MD1") (pin "29") (pinfunction "IO5_29") (pintype "bidirectional"))
    )
    (net (code "53") (name "unconnected-(MD1-IO16-Pad27)") (class "Default")
      (node (ref "MD1") (pin "27") (pinfunction "IO16_27") (pintype "bidirectional"))
    )
    (net (code "54") (name "unconnected-(MD1-IO17-Pad28)") (class "Default")
      (node (ref "MD1") (pin "28") (pinfunction "IO17_28") (pintype "bidirectional"))
    )
    (net (code "55") (name "unconnected-(MD1-IO19-Pad31)") (class "Default")
      (node (ref "MD1") (pin "31") (pinfunction "IO19_31") (pintype "bidirectional"))
    )
    (net (code "56") (name "unconnected-(MD1-IO23-Pad37)") (class "Default")
      (node (ref "MD1") (pin "37") (pinfunction "IO23_37") (pintype "bidirectional"))
    )
    (net (code "57") (name "unconnected-(MD1-IO27-Pad12)") (class "Default")
      (node (ref "MD1") (pin "12") (pinfunction "IO27_12") (pintype "bidirectional"))
    )
    (net (code "58") (name "unconnected-(MD1-IO34-Pad6)") (class "Default")
      (node (ref "MD1") (pin "6") (pinfunction "IO34_6") (pintype "bidirectional"))
    )
    (net (code "59") (name "unconnected-(MD1-IO35-Pad7)") (class "Default")
      (node (ref "MD1") (pin "7") (pinfunction "IO35_7") (pintype "bidirectional"))
    )
    (net (code "60") (name "unconnected-(MD1-NC-Pad32)") (class "Default")
      (node (ref "MD1") (pin "32") (pinfunction "NC_32") (pintype "passive"))
    )
    (net (code "61") (name "unconnected-(MD1-SD0-Pad21)") (class "Default")
      (node (ref "MD1") (pin "21") (pinfunction "SD0_21") (pintype "bidirectional"))
    )
    (net (code "62") (name "unconnected-(MD1-SD1-Pad22)") (class "Default")
      (node (ref "MD1") (pin "22") (pinfunction "SD1_22") (pintype "bidirectional"))
    )
    (net (code "63") (name "unconnected-(MD1-SD2-Pad17)") (class "Default")
      (node (ref "MD1") (pin "17") (pinfunction "SD2_17") (pintype "bidirectional"))
    )
    (net (code "64") (name "unconnected-(MD1-SD3-Pad18)") (class "Default")
      (node (ref "MD1") (pin "18") (pinfunction "SD3_18") (pintype "bidirectional"))
    )
    (net (code "65") (name "unconnected-(MD1-SENSOR_VN-Pad5)") (class "Default")
      (node (ref "MD1") (pin "5") (pinfunction "SENSOR_VN_5") (pintype "bidirectional"))
    )
    (net (code "66") (name "unconnected-(MD1-SENSOR_VP-Pad4)") (class "Default")
      (node (ref "MD1") (pin "4") (pinfunction "SENSOR_VP_4") (pintype "bidirectional"))
    )
    (net (code "67") (name "unconnected-(RELAY-Pad4)") (class "Default")
      (node (ref "RELAY") (pin "4") (pinfunction "4_4") (pintype "passive"))
    )
    (net (code "68") (name "unconnected-(RELAY1-Pad4)") (class "Default")
      (node (ref "RELAY1") (pin "4") (pinfunction "4_4") (pintype "passive"))
    )
    (net (code "69") (name "unconnected-(U2-CHR0-Pad15)") (class "Default")
      (node (ref "U2") (pin "15") (pinfunction "CHR0_15") (pintype "output+no_connect"))
    )
    (net (code "70") (name "unconnected-(U2-CHR1-Pad14)") (class "Default")
      (node (ref "U2") (pin "14") (pinfunction "CHR1_14") (pintype "output+no_connect"))
    )
    (net (code "71") (name "unconnected-(U2-CHREN-Pad13)") (class "Default")
      (node (ref "U2") (pin "13") (pinfunction "CHREN_13") (pintype "output+no_connect"))
    )
    (net (code "72") (name "unconnected-(U2-GPIO.0{slash}TXT-Pad19)") (class "Default")
      (node (ref "U2") (pin "19") (pinfunction "GPIO.0/TXT_19") (pintype "bidirectional+no_connect"))
    )
    (net (code "73") (name "unconnected-(U2-GPIO.1{slash}RXT-Pad18)") (class "Default")
      (node (ref "U2") (pin "18") (pinfunction "GPIO.1/RXT_18") (pintype "bidirectional+no_connect"))
    )
    (net (code "74") (name "unconnected-(U2-GPIO.2{slash}RS485-Pad17)") (class "Default")
      (node (ref "U2") (pin "17") (pinfunction "GPIO.2/RS485_17") (pintype "bidirectional+no_connect"))
    )
    (net (code "75") (name "unconnected-(U2-GPIO.3{slash}WAKEUP-Pad16)") (class "Default")
      (node (ref "U2") (pin "16") (pinfunction "GPIO.3/WAKEUP_16") (pintype "bidirectional+no_connect"))
    )
    (net (code "76") (name "unconnected-(U2-GPIO.4-Pad22)") (class "Default")
      (node (ref "U2") (pin "22") (pinfunction "GPIO.4_22") (pintype "bidirectional+no_connect"))
    )
    (net (code "77") (name "unconnected-(U2-GPIO.5-Pad21)") (class "Default")
      (node (ref "U2") (pin "21") (pinfunction "GPIO.5_21") (pintype "bidirectional+no_connect"))
    )
    (net (code "78") (name "unconnected-(U2-GPIO.6-Pad20)") (class "Default")
      (node (ref "U2") (pin "20") (pinfunction "GPIO.6_20") (pintype "bidirectional+no_connect"))
    )
    (net (code "79") (name "unconnected-(U2-NC-Pad10)") (class "Default")
      (node (ref "U2") (pin "10") (pinfunction "NC_10") (pintype "passive+no_connect"))
    )
    (net (code "80") (name "unconnected-(U2-SUSPEND-Pad12)") (class "Default")
      (node (ref "U2") (pin "12") (pinfunction "SUSPEND_12") (pintype "output+no_connect"))
    )
    (net (code "81") (name "unconnected-(U2-VREGIN-Pad7)") (class "Default")
      (node (ref "U2") (pin "7") (pinfunction "VREGIN_7") (pintype "input+no_connect"))
    )
    (net (code "82") (name "unconnected-(U2-~{CTS}-Pad23)") (class "Default")
      (node (ref "U2") (pin "23") (pinfunction "~{CTS}_23") (pintype "input+no_connect"))
    )
    (net (code "83") (name "unconnected-(U2-~{DCD}-Pad1)") (class "Default")
      (node (ref "U2") (pin "1") (pinfunction "~{DCD}_1") (pintype "passive+no_connect"))
    )
    (net (code "84") (name "unconnected-(U2-~{DSR}-Pad27)") (class "Default")
      (node (ref "U2") (pin "27") (pinfunction "~{DSR}_27") (pintype "input+no_connect"))
    )
    (net (code "85") (name "unconnected-(U2-~{RI}{slash}CLK-Pad2)") (class "Default")
      (node (ref "U2") (pin "2") (pinfunction "~{RI}/CLK_2") (pintype "input+no_connect"))
    )
    (net (code "86") (name "unconnected-(USB-ID-Pad4)") (class "Default")
      (node (ref "USB") (pin "4") (pinfunction "ID_4") (pintype "passive+no_connect"))
    )
  )
)
